# esp8266-UdpTemp.net
KiCad netlist of a schematic drawn in EAGLE
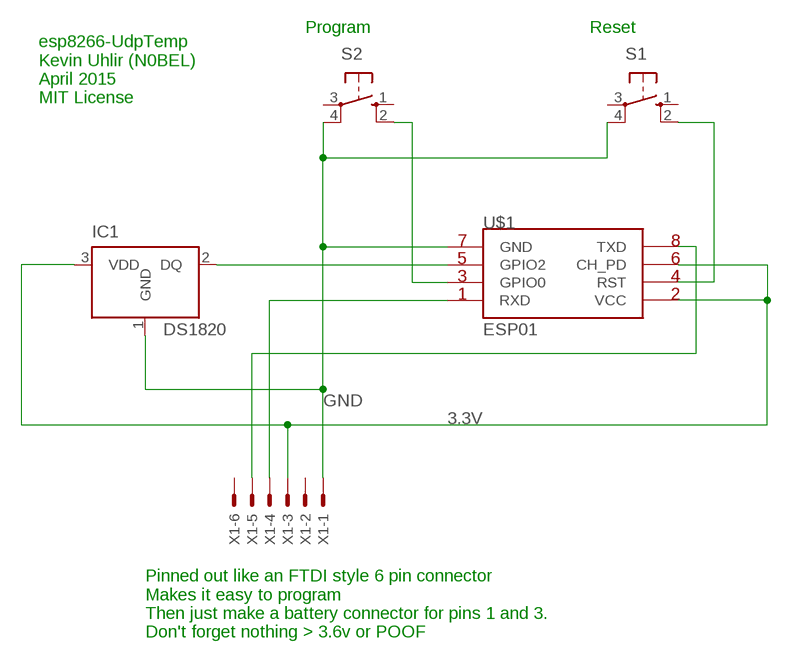
[diagram p0: schematic, sheet 1]

(export (version "E")
  (design (tool "Eeschema 10.0.6"))
  (components
    (comp (ref "IC1")
      (value "DS1820")
      (footprint "eagle-import:TO-92")
      (libsource (lib "eagle-import") (part "DS1820"))
    )
    (comp (ref "S1")
      (value "10-XX")
      (footprint "eagle-import:B3F-10XX")
      (fields (field (name "MPN") "B3F-1000"))
      (libsource (lib "eagle-import") (part "10-XX"))
    )
    (comp (ref "S2")
      (value "10-XX")
      (footprint "eagle-import:B3F-10XX")
      (fields (field (name "MPN") "B3F-1000"))
      (libsource (lib "eagle-import") (part "10-XX"))
    )
    (comp (ref "U$1")
      (value "ESP01")
      (footprint "eagle-import:ESP01")
      (libsource (lib "eagle-import") (part "ESP01"))
    )
    (comp (ref "X1")
      (value "22-23-2061")
      (footprint "eagle-import:22-23-2061")
      (fields (field (name "MF") "MOLEX"))
      (libsource (lib "eagle-import") (part "22-23-2061"))
    )
  )
  (nets
    (net (code "1") (name "/3.3V") (class "Default")
      (node (ref "IC1") (pin "3") (pinfunction "VDD_3") (pintype "input"))
      (node (ref "U$1") (pin "CH_PD") (pinfunction "CH_PD_CH_PD") (pintype "bidirectional"))
      (node (ref "U$1") (pin "VCC") (pinfunction "VCC_VCC") (pintype "bidirectional"))
      (node (ref "X1") (pin "3") (pinfunction "S_3") (pintype "passive"))
    )
    (net (code "2") (name "/GND") (class "Default")
      (node (ref "IC1") (pin "1") (pinfunction "GND_1") (pintype "power_in"))
      (node (ref "S1") (pin "4") (pinfunction "P1_4") (pintype "passive"))
      (node (ref "S2") (pin "4") (pinfunction "P1_4") (pintype "passive"))
      (node (ref "U$1") (pin "GND") (pinfunction "GND_GND") (pintype "bidirectional"))
      (node (ref "X1") (pin "1") (pinfunction "S_1") (pintype "passive"))
    )
    (net (code "3") (name "Net-(IC1-DQ)") (class "Default")
      (node (ref "IC1") (pin "2") (pinfunction "DQ_2") (pintype "output"))
      (node (ref "U$1") (pin "GPIO2") (pinfunction "GPIO2_GPIO2") (pintype "bidirectional"))
    )
    (net (code "4") (name "Net-(S1-S1)") (class "Default")
      (node (ref "S1") (pin "2") (pinfunction "S1_2") (pintype "passive"))
      (node (ref "U$1") (pin "RST") (pinfunction "RST_RST") (pintype "bidirectional"))
    )
    (net (code "5") (name "Net-(S2-S1)") (class "Default")
      (node (ref "S2") (pin "2") (pinfunction "S1_2") (pintype "passive"))
      (node (ref "U$1") (pin "GPIO0") (pinfunction "GPIO0_GPIO0") (pintype "bidirectional"))
    )
    (net (code "6") (name "Net-(U$1-RXD)") (class "Default")
      (node (ref "U$1") (pin "RX") (pinfunction "RXD_RX") (pintype "bidirectional"))
      (node (ref "X1") (pin "4") (pinfunction "S_4") (pintype "passive"))
    )
    (net (code "7") (name "Net-(U$1-TXD)") (class "Default")
      (node (ref "U$1") (pin "TX") (pinfunction "TXD_TX") (pintype "bidirectional"))
      (node (ref "X1") (pin "5") (pinfunction "S_5") (pintype "passive"))
    )
    (net (code "8") (name "unconnected-(S1-P-Pad3)") (class "Default")
      (node (ref "S1") (pin "3") (pinfunction "P_3") (pintype "passive"))
    )
    (net (code "9") (name "unconnected-(S1-S-Pad1)") (class "Default")
      (node (ref "S1") (pin "1") (pinfunction "S_1") (pintype "passive"))
    )
    (net (code "10") (name "unconnected-(S2-P-Pad3)") (class "Default")
      (node (ref "S2") (pin "3") (pinfunction "P_3") (pintype "passive"))
    )
    (net (code "11") (name "unconnected-(S2-S-Pad1)") (class "Default")
      (node (ref "S2") (pin "1") (pinfunction "S_1") (pintype "passive"))
    )
    (net (code "12") (name "unconnected-(X1B-S-Pad2)") (class "Default")
      (node (ref "X1") (pin "2") (pinfunction "S_2") (pintype "passive"))
    )
    (net (code "13") (name "unconnected-(X1F-S-Pad6)") (class "Default")
      (node (ref "X1") (pin "6") (pinfunction "S_6") (pintype "passive"))
    )
  )
)
